# 7SEGSHIELDTHERMISTOR.net
KiCad netlist of a schematic drawn in EAGLE
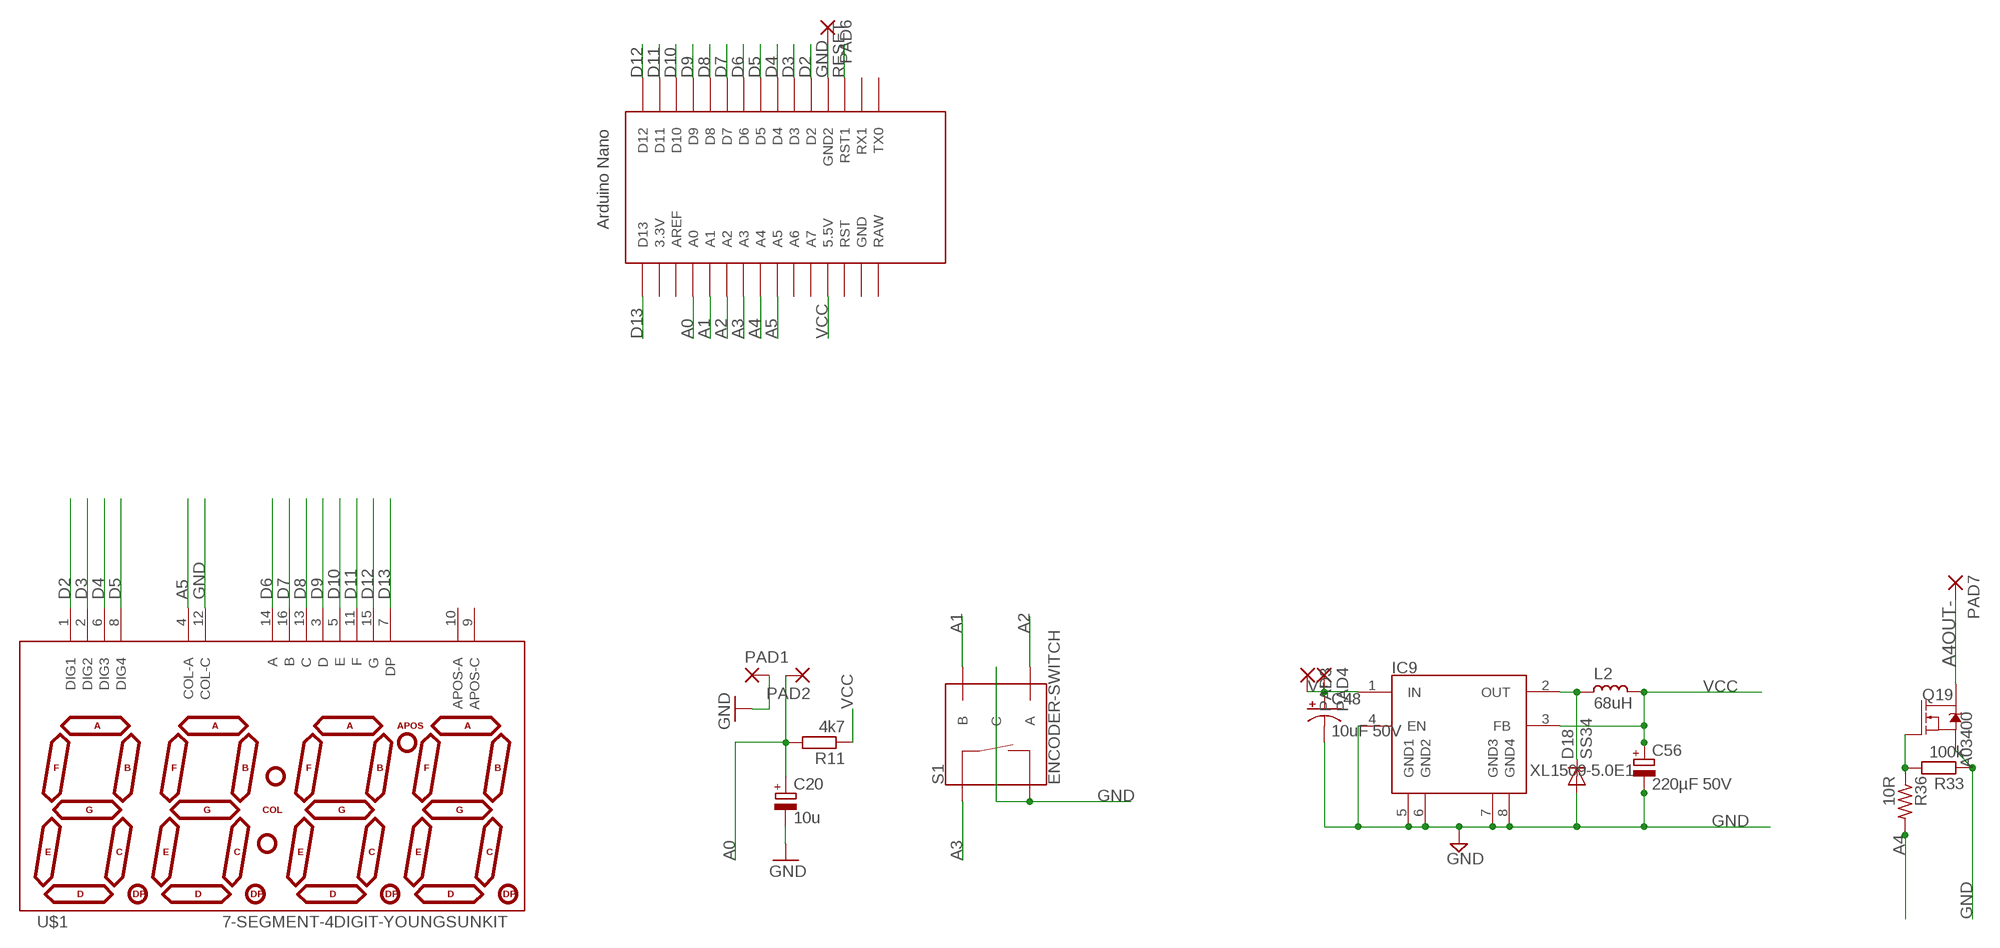
[diagram p0: schematic, sheet 1]

(export (version "E")
  (design (tool "Eeschema 10.0.6"))
  (components
    (comp (ref "C20")
      (value "10u")
      (footprint "eagle-import:A_3216-18W")
      (libsource (lib "eagle-import") (part "CPOL-EUA/3216-18W"))
    )
    (comp (ref "C48")
      (value "10uF 50V")
      (footprint "eagle-import:EIA3216")
      (libsource (lib "eagle-import") (part "CAP_POL1206"))
    )
    (comp (ref "C56")
      (value "220µF 50V")
      (footprint "eagle-import:E2,5-6E")
      (libsource (lib "eagle-import") (part "rcl_334_CPOL-EUE2,5-6E"))
    )
    (comp (ref "D18")
      (value "SS34")
      (footprint "eagle-import:DO-214AC")
      (libsource (lib "eagle-import") (part "DIODE-DO-214AC"))
    )
    (comp (ref "IC9")
      (value "XL1509-5.0E1")
      (footprint "eagle-import:SO08")
      (libsource (lib "eagle-import") (part "XL1509"))
    )
    (comp (ref "L2")
      (value "68uH")
      (footprint "eagle-import:CD75")
      (libsource (lib "eagle-import") (part "L_CD75"))
    )
    (comp (ref "PAD1")
      (value "2,54/1,1")
      (footprint "eagle-import:2,54_1,1")
      (libsource (lib "eagle-import") (part "2,54/1,1"))
    )
    (comp (ref "PAD2")
      (value "2,54/1,1")
      (footprint "eagle-import:2,54_1,1")
      (libsource (lib "eagle-import") (part "2,54/1,1"))
    )
    (comp (ref "PAD3")
      (value "2,54/1,1")
      (footprint "eagle-import:2,54_1,1")
      (libsource (lib "eagle-import") (part "2,54/1,1"))
    )
    (comp (ref "PAD4")
      (value "2,54/1,1")
      (footprint "eagle-import:2,54_1,1")
      (libsource (lib "eagle-import") (part "2,54/1,1"))
    )
    (comp (ref "PAD6")
      (value "2,54/1,1")
      (footprint "eagle-import:2,54_1,1")
      (libsource (lib "eagle-import") (part "2,54/1,1"))
    )
    (comp (ref "PAD7")
      (value "2,54/1,1")
      (footprint "eagle-import:2,54_1,1")
      (libsource (lib "eagle-import") (part "2,54/1,1"))
    )
    (comp (ref "Q19")
      (value "A03400")
      (footprint "eagle-import:SOT23-3@1")
      (libsource (lib "eagle-import") (part "MOSFET-NCH-AO3404A"))
    )
    (comp (ref "R11")
      (value "4k7")
      (footprint "eagle-import:M1206")
      (libsource (lib "eagle-import") (part "R-EU_M1206"))
    )
    (comp (ref "R33")
      (value "100k")
      (footprint "eagle-import:R1206")
      (libsource (lib "eagle-import") (part "resistor_348_R-EU_R1206"))
    )
    (comp (ref "R36")
      (value "10R")
      (footprint "eagle-import:R1206@1")
      (libsource (lib "eagle-import") (part "R-US_R1206"))
    )
    (comp (ref "S1")
      (value "ENCODER-SWITCH")
      (footprint "eagle-import:ROTARY_ENC_PLAIN")
      (libsource (lib "eagle-import") (part "ENCODER-SWITCH"))
    )
    (comp (ref "U$1")
      (value "7-SEGMENT-4DIGIT-YOUNGSUNKIT")
      (footprint "eagle-import:7-SEGMENT-4DIGIT-YOUNGSUN-KIT")
      (libsource (lib "eagle-import") (part "7-SEGMENT-4DIGIT-YOUNGSUNKIT"))
    )
    (comp (ref "U$2")
      (value "NANO")
      (footprint "eagle-import:NANO")
      (libsource (lib "eagle-import") (part "NANO"))
    )
  )
  (nets
    (net (code "1") (name "/A0") (class "Default")
      (node (ref "C20") (pin "+") (pinfunction "+_+") (pintype "passive"))
      (node (ref "PAD2") (pin "1") (pinfunction "P_1") (pintype "passive"))
      (node (ref "R11") (pin "2") (pinfunction "2_2") (pintype "passive"))
      (node (ref "U$2") (pin "A0") (pinfunction "A0_A0") (pintype "bidirectional"))
    )
    (net (code "2") (name "/A1") (class "Default")
      (node (ref "S1") (pin "B") (pinfunction "B_B") (pintype "bidirectional"))
      (node (ref "U$2") (pin "A1") (pinfunction "A1_A1") (pintype "bidirectional"))
    )
    (net (code "3") (name "/A2") (class "Default")
      (node (ref "S1") (pin "A") (pinfunction "A_A") (pintype "bidirectional"))
      (node (ref "U$2") (pin "A2") (pinfunction "A2_A2") (pintype "bidirectional"))
    )
    (net (code "4") (name "/A3") (class "Default")
      (node (ref "S1") (pin "SW+") (pinfunction "SW+_SW+") (pintype "bidirectional"))
      (node (ref "U$2") (pin "A3") (pinfunction "A3_A3") (pintype "bidirectional"))
    )
    (net (code "5") (name "/A4") (class "Default")
      (node (ref "R36") (pin "2") (pinfunction "2_2") (pintype "passive"))
      (node (ref "U$2") (pin "A4") (pinfunction "A4_A4") (pintype "bidirectional"))
    )
    (net (code "6") (name "/A4OUT-") (class "Default")
      (node (ref "PAD7") (pin "1") (pinfunction "P_1") (pintype "passive"))
      (node (ref "Q19") (pin "3") (pinfunction "D_3") (pintype "bidirectional"))
    )
    (net (code "7") (name "/A5") (class "Default")
      (node (ref "U$1") (pin "4") (pinfunction "COL-A_4") (pintype "bidirectional"))
      (node (ref "U$2") (pin "A5") (pinfunction "A5_A5") (pintype "bidirectional"))
    )
    (net (code "8") (name "/D2") (class "Default")
      (node (ref "U$1") (pin "1") (pinfunction "DIG1_1") (pintype "bidirectional"))
      (node (ref "U$2") (pin "D2") (pinfunction "D2_D2") (pintype "bidirectional"))
    )
    (net (code "9") (name "/D3") (class "Default")
      (node (ref "U$1") (pin "2") (pinfunction "DIG2_2") (pintype "bidirectional"))
      (node (ref "U$2") (pin "D3") (pinfunction "D3_D3") (pintype "bidirectional"))
    )
    (net (code "10") (name "/D4") (class "Default")
      (node (ref "U$1") (pin "6") (pinfunction "DIG3_6") (pintype "bidirectional"))
      (node (ref "U$2") (pin "D4") (pinfunction "D4_D4") (pintype "bidirectional"))
    )
    (net (code "11") (name "/D5") (class "Default")
      (node (ref "U$1") (pin "8") (pinfunction "DIG4_8") (pintype "bidirectional"))
      (node (ref "U$2") (pin "D5") (pinfunction "D5_D5") (pintype "bidirectional"))
    )
    (net (code "12") (name "/D6") (class "Default")
      (node (ref "U$1") (pin "14") (pinfunction "A_14") (pintype "bidirectional"))
      (node (ref "U$2") (pin "D6") (pinfunction "D6_D6") (pintype "bidirectional"))
    )
    (net (code "13") (name "/D7") (class "Default")
      (node (ref "U$1") (pin "16") (pinfunction "B_16") (pintype "bidirectional"))
      (node (ref "U$2") (pin "D7") (pinfunction "D7_D7") (pintype "bidirectional"))
    )
    (net (code "14") (name "/D8") (class "Default")
      (node (ref "U$1") (pin "13") (pinfunction "C_13") (pintype "bidirectional"))
      (node (ref "U$2") (pin "D8") (pinfunction "D8_D8") (pintype "bidirectional"))
    )
    (net (code "15") (name "/D9") (class "Default")
      (node (ref "U$1") (pin "3") (pinfunction "D_3") (pintype "bidirectional"))
      (node (ref "U$2") (pin "D9") (pinfunction "D9_D9") (pintype "bidirectional"))
    )
    (net (code "16") (name "/D10") (class "Default")
      (node (ref "U$1") (pin "5") (pinfunction "E_5") (pintype "bidirectional"))
      (node (ref "U$2") (pin "D10") (pinfunction "D10_D10") (pintype "bidirectional"))
    )
    (net (code "17") (name "/D11") (class "Default")
      (node (ref "U$1") (pin "11") (pinfunction "F_11") (pintype "bidirectional"))
      (node (ref "U$2") (pin "D11") (pinfunction "D11_D11") (pintype "bidirectional"))
    )
    (net (code "18") (name "/D12") (class "Default")
      (node (ref "U$1") (pin "15") (pinfunction "G_15") (pintype "bidirectional"))
      (node (ref "U$2") (pin "D12") (pinfunction "D12_D12") (pintype "bidirectional"))
    )
    (net (code "19") (name "/D13") (class "Default")
      (node (ref "U$1") (pin "7") (pinfunction "DP_7") (pintype "bidirectional"))
      (node (ref "U$2") (pin "D13") (pinfunction "D13_D13") (pintype "bidirectional"))
    )
    (net (code "20") (name "/RESET") (class "Default")
      (node (ref "U$2") (pin "RST1") (pinfunction "RST1_RST1") (pintype "bidirectional"))
    )
    (net (code "21") (name "/V+") (class "Default")
      (node (ref "C48") (pin "A") (pinfunction "+_A") (pintype "passive"))
      (node (ref "IC9") (pin "1") (pinfunction "IN_1") (pintype "bidirectional"))
      (node (ref "PAD3") (pin "1") (pinfunction "P_1") (pintype "passive"))
      (node (ref "PAD4") (pin "1") (pinfunction "P_1") (pintype "passive"))
    )
    (net (code "22") (name "/VCC") (class "Default")
      (node (ref "C56") (pin "+") (pinfunction "+_+") (pintype "passive"))
      (node (ref "IC9") (pin "3") (pinfunction "FB_3") (pintype "bidirectional"))
      (node (ref "L2") (pin "1") (pinfunction "1_1") (pintype "passive"))
      (node (ref "R11") (pin "1") (pinfunction "1_1") (pintype "passive"))
      (node (ref "U$2") (pin "5V") (pinfunction "5.5V_5V") (pintype "bidirectional"))
    )
    (net (code "23") (name "GND") (class "Default")
      (node (ref "C20") (pin "-") (pinfunction "-_-") (pintype "passive"))
      (node (ref "C48") (pin "C") (pinfunction "-_C") (pintype "passive"))
      (node (ref "C56") (pin "-") (pinfunction "-_-") (pintype "passive"))
      (node (ref "D18") (pin "2") (pinfunction "A_2") (pintype "passive"))
      (node (ref "IC9") (pin "4") (pinfunction "EN_4") (pintype "bidirectional"))
      (node (ref "IC9") (pin "5") (pinfunction "GND1_5") (pintype "bidirectional"))
      (node (ref "IC9") (pin "6") (pinfunction "GND2_6") (pintype "bidirectional"))
      (node (ref "IC9") (pin "7") (pinfunction "GND3_7") (pintype "bidirectional"))
      (node (ref "IC9") (pin "8") (pinfunction "GND4_8") (pintype "bidirectional"))
      (node (ref "PAD1") (pin "1") (pinfunction "P_1") (pintype "passive"))
      (node (ref "PAD6") (pin "1") (pinfunction "P_1") (pintype "passive"))
      (node (ref "Q19") (pin "2") (pinfunction "S_2") (pintype "bidirectional"))
      (node (ref "R33") (pin "1") (pinfunction "1_1") (pintype "passive"))
      (node (ref "S1") (pin "C") (pinfunction "C_C") (pintype "bidirectional"))
      (node (ref "S1") (pin "SW-") (pinfunction "SW-_SW-") (pintype "bidirectional"))
      (node (ref "U$1") (pin "12") (pinfunction "COL-C_12") (pintype "bidirectional"))
      (node (ref "U$2") (pin "GND1") (pinfunction "GND2_GND1") (pintype "bidirectional"))
    )
    (net (code "24") (name "Net-(D18-C)") (class "Default")
      (node (ref "D18") (pin "1") (pinfunction "C_1") (pintype "passive"))
      (node (ref "IC9") (pin "2") (pinfunction "OUT_2") (pintype "bidirectional"))
      (node (ref "L2") (pin "2") (pinfunction "2_2") (pintype "passive"))
    )
    (net (code "25") (name "Net-(Q19-G)") (class "Default")
      (node (ref "Q19") (pin "1") (pinfunction "G_1") (pintype "bidirectional"))
      (node (ref "R33") (pin "2") (pinfunction "2_2") (pintype "passive"))
      (node (ref "R36") (pin "1") (pinfunction "1_1") (pintype "passive"))
    )
    (net (code "26") (name "unconnected-(U$1-APOS-A-Pad10)") (class "Default")
      (node (ref "U$1") (pin "10") (pinfunction "APOS-A_10") (pintype "bidirectional"))
    )
    (net (code "27") (name "unconnected-(U$1-APOS-C-Pad9)") (class "Default")
      (node (ref "U$1") (pin "9") (pinfunction "APOS-C_9") (pintype "bidirectional"))
    )
    (net (code "28") (name "unconnected-(U$2-Pad3.3V)") (class "Default")
      (node (ref "U$2") (pin "3.3V") (pinfunction "3.3V_3.3V") (pintype "bidirectional"))
    )
    (net (code "29") (name "unconnected-(U$2-PadA6)") (class "Default")
      (node (ref "U$2") (pin "A6") (pinfunction "A6_A6") (pintype "bidirectional"))
    )
    (net (code "30") (name "unconnected-(U$2-PadA7)") (class "Default")
      (node (ref "U$2") (pin "A7") (pinfunction "A7_A7") (pintype "bidirectional"))
    )
    (net (code "31") (name "unconnected-(U$2-PadAREF)") (class "Default")
      (node (ref "U$2") (pin "AREF") (pinfunction "AREF_AREF") (pintype "bidirectional"))
    )
    (net (code "32") (name "unconnected-(U$2-PadGND)") (class "Default")
      (node (ref "U$2") (pin "GND") (pinfunction "GND_GND") (pintype "bidirectional"))
    )
    (net (code "33") (name "unconnected-(U$2-PadICSP1)") (class "Default")
      (node (ref "U$2") (pin "ICSP1") (pinfunction "ICSP1_ICSP1") (pintype "bidirectional"))
    )
    (net (code "34") (name "unconnected-(U$2-PadICSP2)") (class "Default")
      (node (ref "U$2") (pin "ICSP2") (pinfunction "ICSP2_ICSP2") (pintype "bidirectional"))
    )
    (net (code "35") (name "unconnected-(U$2-PadICSP3)") (class "Default")
      (node (ref "U$2") (pin "ICSP3") (pinfunction "ICSP3_ICSP3") (pintype "bidirectional"))
    )
    (net (code "36") (name "unconnected-(U$2-PadICSP4)") (class "Default")
      (node (ref "U$2") (pin "ICSP4") (pinfunction "ICSP4_ICSP4") (pintype "bidirectional"))
    )
    (net (code "37") (name "unconnected-(U$2-PadICSP5)") (class "Default")
      (node (ref "U$2") (pin "ICSP5") (pinfunction "ICSP5_ICSP5") (pintype "bidirectional"))
    )
    (net (code "38") (name "unconnected-(U$2-PadICSP6)") (class "Default")
      (node (ref "U$2") (pin "ICSP6") (pinfunction "ICSP6_ICSP6") (pintype "bidirectional"))
    )
    (net (code "39") (name "unconnected-(U$2-PadRAW)") (class "Default")
      (node (ref "U$2") (pin "RAW") (pinfunction "RAW_RAW") (pintype "bidirectional"))
    )
    (net (code "40") (name "unconnected-(U$2-PadRST)") (class "Default")
      (node (ref "U$2") (pin "RST") (pinfunction "RST_RST") (pintype "bidirectional"))
    )
    (net (code "41") (name "unconnected-(U$2-PadRX1)") (class "Default")
      (node (ref "U$2") (pin "RX1") (pinfunction "RX1_RX1") (pintype "bidirectional"))
    )
    (net (code "42") (name "unconnected-(U$2-PadTX0)") (class "Default")
      (node (ref "U$2") (pin "TX0") (pinfunction "TX0_TX0") (pintype "bidirectional"))
    )
  )
)
